# Audio_Amp.net
KiCad netlist of a schematic drawn in Altium Designer
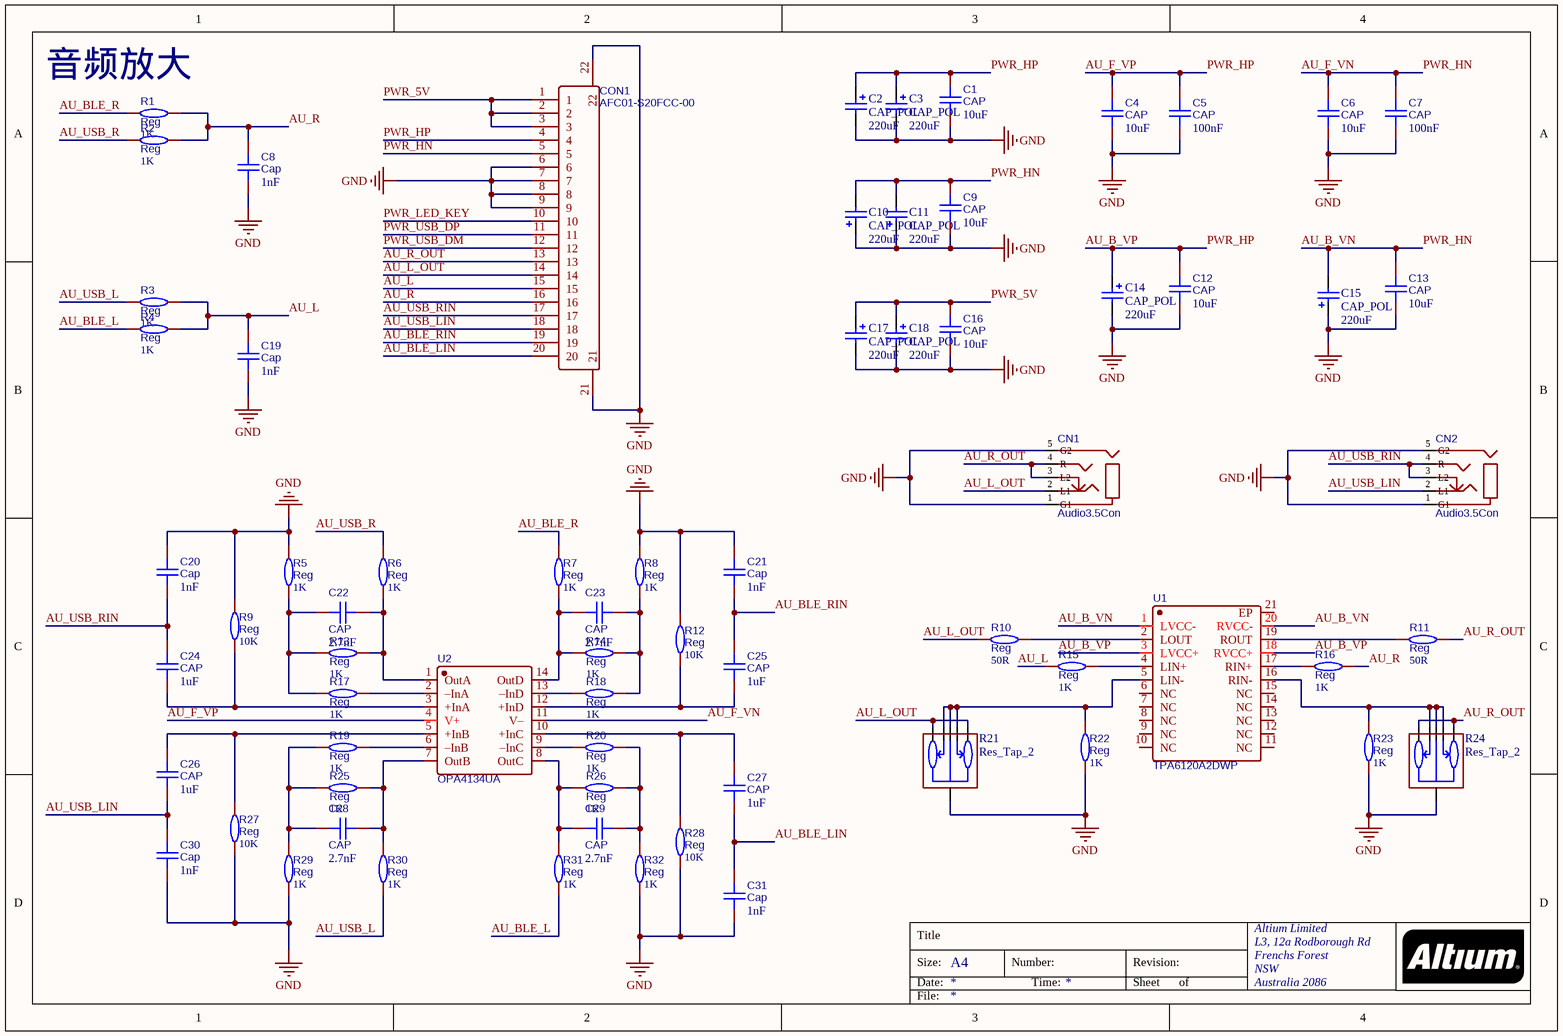
[diagram p0: Audio_Amp.SchDoc]

(export (version "E")
  (design (tool "Eeschema 10.0.6"))
  (components
    (comp (ref "C1")
      (value "CAP")
      (footprint "C0603")
      (description "Cap")
      (fields
        (field (name "BOM_SUPPLIER PART") "C302008")
        (field (name "BOM_MANUFACTURER PART") "0603B103K101CT")
        (field (name "ALTIUM_VALUE") "10uF")
        (field (name "CONTRIBUTOR") "LCSC")
      )
      (libsource (lib "Levent_lib") (part "CAP"))
    )
    (comp (ref "C2")
      (value "CAP_POL")
      (footprint "CAP_SMD_6.3mm")
      (description "极性电容")
      (fields (field (name "ALTIUM_VALUE") "220uF"))
      (libsource (lib "Levent_lib") (part "CAP_POL"))
    )
    (comp (ref "C3")
      (value "CAP_POL")
      (footprint "CAP_SMD_6.3mm")
      (description "极性电容")
      (fields (field (name "ALTIUM_VALUE") "220uF"))
      (libsource (lib "Levent_lib") (part "CAP_POL"))
    )
    (comp (ref "C4")
      (value "CAP")
      (footprint "C0603")
      (description "Cap")
      (fields
        (field (name "BOM_SUPPLIER PART") "C302008")
        (field (name "BOM_MANUFACTURER PART") "0603B103K101CT")
        (field (name "ALTIUM_VALUE") "10uF")
        (field (name "CONTRIBUTOR") "LCSC")
      )
      (libsource (lib "Levent_lib") (part "CAP"))
    )
    (comp (ref "C5")
      (value "CAP")
      (footprint "C0603")
      (description "Cap")
      (fields
        (field (name "BOM_SUPPLIER PART") "C302008")
        (field (name "BOM_MANUFACTURER PART") "0603B103K101CT")
        (field (name "ALTIUM_VALUE") "100nF")
        (field (name "CONTRIBUTOR") "LCSC")
      )
      (libsource (lib "Levent_lib") (part "CAP"))
    )
    (comp (ref "C6")
      (value "CAP")
      (footprint "C0603")
      (description "Cap")
      (fields
        (field (name "BOM_SUPPLIER PART") "C302008")
        (field (name "BOM_MANUFACTURER PART") "0603B103K101CT")
        (field (name "ALTIUM_VALUE") "10uF")
        (field (name "CONTRIBUTOR") "LCSC")
      )
      (libsource (lib "Levent_lib") (part "CAP"))
    )
    (comp (ref "C7")
      (value "CAP")
      (footprint "C0603")
      (description "Cap")
      (fields
        (field (name "BOM_SUPPLIER PART") "C302008")
        (field (name "BOM_MANUFACTURER PART") "0603B103K101CT")
        (field (name "ALTIUM_VALUE") "100nF")
        (field (name "CONTRIBUTOR") "LCSC")
      )
      (libsource (lib "Levent_lib") (part "CAP"))
    )
    (comp (ref "C8")
      (value "Cap")
      (footprint "C0603")
      (fields
        (field (name "BOM_SUPPLIER PART") "C302008")
        (field (name "BOM_MANUFACTURER PART") "0603B103K101CT")
        (field (name "ALTIUM_VALUE") "1nF")
        (field (name "CONTRIBUTOR") "LCSC")
      )
      (libsource (lib "Levent_lib") (part "CAP"))
    )
    (comp (ref "C9")
      (value "CAP")
      (footprint "C0603")
      (description "Cap")
      (fields
        (field (name "BOM_SUPPLIER PART") "C302008")
        (field (name "BOM_MANUFACTURER PART") "0603B103K101CT")
        (field (name "ALTIUM_VALUE") "10uF")
        (field (name "CONTRIBUTOR") "LCSC")
      )
      (libsource (lib "Levent_lib") (part "CAP"))
    )
    (comp (ref "C10")
      (value "CAP_POL")
      (footprint "CAP_SMD_6.3mm")
      (description "极性电容")
      (fields (field (name "ALTIUM_VALUE") "220uF"))
      (libsource (lib "Levent_lib") (part "CAP_POL"))
    )
    (comp (ref "C11")
      (value "CAP_POL")
      (footprint "CAP_SMD_6.3mm")
      (description "极性电容")
      (fields (field (name "ALTIUM_VALUE") "220uF"))
      (libsource (lib "Levent_lib") (part "CAP_POL"))
    )
    (comp (ref "C12")
      (value "CAP")
      (footprint "C0603")
      (description "Cap")
      (fields
        (field (name "BOM_SUPPLIER PART") "C302008")
        (field (name "BOM_MANUFACTURER PART") "0603B103K101CT")
        (field (name "ALTIUM_VALUE") "10uF")
        (field (name "CONTRIBUTOR") "LCSC")
      )
      (libsource (lib "Levent_lib") (part "CAP"))
    )
    (comp (ref "C13")
      (value "CAP")
      (footprint "C0603")
      (description "Cap")
      (fields
        (field (name "BOM_SUPPLIER PART") "C302008")
        (field (name "BOM_MANUFACTURER PART") "0603B103K101CT")
        (field (name "ALTIUM_VALUE") "10uF")
        (field (name "CONTRIBUTOR") "LCSC")
      )
      (libsource (lib "Levent_lib") (part "CAP"))
    )
    (comp (ref "C14")
      (value "CAP_POL")
      (footprint "CAP_SMD_6.3mm")
      (description "极性电容")
      (fields (field (name "ALTIUM_VALUE") "220uF"))
      (libsource (lib "Levent_lib") (part "CAP_POL"))
    )
    (comp (ref "C15")
      (value "CAP_POL")
      (footprint "CAP_SMD_6.3mm")
      (description "极性电容")
      (fields (field (name "ALTIUM_VALUE") "220uF"))
      (libsource (lib "Levent_lib") (part "CAP_POL"))
    )
    (comp (ref "C16")
      (value "CAP")
      (footprint "C0603")
      (description "Cap")
      (fields
        (field (name "BOM_SUPPLIER PART") "C302008")
        (field (name "BOM_MANUFACTURER PART") "0603B103K101CT")
        (field (name "ALTIUM_VALUE") "10uF")
        (field (name "CONTRIBUTOR") "LCSC")
      )
      (libsource (lib "Levent_lib") (part "CAP"))
    )
    (comp (ref "C17")
      (value "CAP_POL")
      (footprint "CAP_SMD_6.3mm")
      (description "极性电容")
      (fields (field (name "ALTIUM_VALUE") "220uF"))
      (libsource (lib "Levent_lib") (part "CAP_POL"))
    )
    (comp (ref "C18")
      (value "CAP_POL")
      (footprint "CAP_SMD_6.3mm")
      (description "极性电容")
      (fields (field (name "ALTIUM_VALUE") "220uF"))
      (libsource (lib "Levent_lib") (part "CAP_POL"))
    )
    (comp (ref "C19")
      (value "Cap")
      (footprint "C0603")
      (fields
        (field (name "BOM_SUPPLIER PART") "C302008")
        (field (name "BOM_MANUFACTURER PART") "0603B103K101CT")
        (field (name "ALTIUM_VALUE") "1nF")
        (field (name "CONTRIBUTOR") "LCSC")
      )
      (libsource (lib "Levent_lib") (part "CAP"))
    )
    (comp (ref "C20")
      (value "Cap")
      (footprint "C0603")
      (fields
        (field (name "BOM_SUPPLIER PART") "C302008")
        (field (name "BOM_MANUFACTURER PART") "0603B103K101CT")
        (field (name "ALTIUM_VALUE") "1nF")
        (field (name "CONTRIBUTOR") "LCSC")
      )
      (libsource (lib "Levent_lib") (part "CAP"))
    )
    (comp (ref "C21")
      (value "Cap")
      (footprint "C0603")
      (fields
        (field (name "BOM_SUPPLIER PART") "C302008")
        (field (name "BOM_MANUFACTURER PART") "0603B103K101CT")
        (field (name "ALTIUM_VALUE") "1nF")
        (field (name "CONTRIBUTOR") "LCSC")
      )
      (libsource (lib "Levent_lib") (part "CAP"))
    )
    (comp (ref "C22")
      (value "CAP")
      (footprint "C0603")
      (description "Cap")
      (fields
        (field (name "BOM_SUPPLIER PART") "C302008")
        (field (name "BOM_MANUFACTURER PART") "0603B103K101CT")
        (field (name "ALTIUM_VALUE") "2.7nF")
        (field (name "CONTRIBUTOR") "LCSC")
      )
      (libsource (lib "Levent_lib") (part "CAP"))
    )
    (comp (ref "C23")
      (value "CAP")
      (footprint "C0603")
      (description "Cap")
      (fields
        (field (name "BOM_SUPPLIER PART") "C302008")
        (field (name "BOM_MANUFACTURER PART") "0603B103K101CT")
        (field (name "ALTIUM_VALUE") "2.7nF")
        (field (name "CONTRIBUTOR") "LCSC")
      )
      (libsource (lib "Levent_lib") (part "CAP"))
    )
    (comp (ref "C24")
      (value "CAP")
      (footprint "C0603")
      (description "Cap")
      (fields
        (field (name "BOM_SUPPLIER PART") "C302008")
        (field (name "BOM_MANUFACTURER PART") "0603B103K101CT")
        (field (name "ALTIUM_VALUE") "1uF")
        (field (name "CONTRIBUTOR") "LCSC")
      )
      (libsource (lib "Levent_lib") (part "CAP"))
    )
    (comp (ref "C25")
      (value "CAP")
      (footprint "C0603")
      (description "Cap")
      (fields
        (field (name "BOM_SUPPLIER PART") "C302008")
        (field (name "BOM_MANUFACTURER PART") "0603B103K101CT")
        (field (name "ALTIUM_VALUE") "1uF")
        (field (name "CONTRIBUTOR") "LCSC")
      )
      (libsource (lib "Levent_lib") (part "CAP"))
    )
    (comp (ref "C26")
      (value "CAP")
      (footprint "C0603")
      (description "Cap")
      (fields
        (field (name "BOM_SUPPLIER PART") "C302008")
        (field (name "BOM_MANUFACTURER PART") "0603B103K101CT")
        (field (name "ALTIUM_VALUE") "1uF")
        (field (name "CONTRIBUTOR") "LCSC")
      )
      (libsource (lib "Levent_lib") (part "CAP"))
    )
    (comp (ref "C27")
      (value "CAP")
      (footprint "C0603")
      (description "Cap")
      (fields
        (field (name "BOM_SUPPLIER PART") "C302008")
        (field (name "BOM_MANUFACTURER PART") "0603B103K101CT")
        (field (name "ALTIUM_VALUE") "1uF")
        (field (name "CONTRIBUTOR") "LCSC")
      )
      (libsource (lib "Levent_lib") (part "CAP"))
    )
    (comp (ref "C28")
      (value "CAP")
      (footprint "C0603")
      (description "Cap")
      (fields
        (field (name "BOM_SUPPLIER PART") "C302008")
        (field (name "BOM_MANUFACTURER PART") "0603B103K101CT")
        (field (name "ALTIUM_VALUE") "2.7nF")
        (field (name "CONTRIBUTOR") "LCSC")
      )
      (libsource (lib "Levent_lib") (part "CAP"))
    )
    (comp (ref "C29")
      (value "CAP")
      (footprint "C0603")
      (description "Cap")
      (fields
        (field (name "BOM_SUPPLIER PART") "C302008")
        (field (name "BOM_MANUFACTURER PART") "0603B103K101CT")
        (field (name "ALTIUM_VALUE") "2.7nF")
        (field (name "CONTRIBUTOR") "LCSC")
      )
      (libsource (lib "Levent_lib") (part "CAP"))
    )
    (comp (ref "C30")
      (value "Cap")
      (footprint "C0603")
      (fields
        (field (name "BOM_SUPPLIER PART") "C302008")
        (field (name "BOM_MANUFACTURER PART") "0603B103K101CT")
        (field (name "ALTIUM_VALUE") "1nF")
        (field (name "CONTRIBUTOR") "LCSC")
      )
      (libsource (lib "Levent_lib") (part "CAP"))
    )
    (comp (ref "C31")
      (value "Cap")
      (footprint "C0603")
      (fields
        (field (name "BOM_SUPPLIER PART") "C302008")
        (field (name "BOM_MANUFACTURER PART") "0603B103K101CT")
        (field (name "ALTIUM_VALUE") "1nF")
        (field (name "CONTRIBUTOR") "LCSC")
      )
      (libsource (lib "Levent_lib") (part "CAP"))
    )
    (comp (ref "CN1")
      (value "Audio3.5Con")
      (footprint "Audio3.5_3Pin")
      (description "3.5mm 3Pin 音频接口")
      (fields
        (field (name "BOM_SUPPLIER PART") "C2837065")
        (field (name "BOM_MANUFACTURER PART") "PJ-393")
        (field (name "CONTRIBUTOR") "LCSC")
      )
      (libsource (lib "Levent_lib") (part "AudioCon3"))
    )
    (comp (ref "CN2")
      (value "Audio3.5Con")
      (footprint "Audio3.5_3Pin")
      (description "3.5mm 3Pin 音频接口")
      (fields
        (field (name "BOM_SUPPLIER PART") "C2837065")
        (field (name "BOM_MANUFACTURER PART") "PJ-393")
        (field (name "CONTRIBUTOR") "LCSC")
      )
      (libsource (lib "Levent_lib") (part "AudioCon3"))
    )
    (comp (ref "CON1")
      (value "AFC01-S20FCC-00")
      (footprint "FPC-SMD_20P_0.5")
      (description "FPC连接器20Pin")
      (fields (field (name "BOM_SUPPLIER PART") "C262274") (field (name "CONTRIBUTOR") "LCSC"))
      (libsource (lib "Levent_lib") (part "FPC_CONN_20"))
    )
    (comp (ref "R1")
      (value "Reg")
      (footprint "R0603")
      (description "电阻")
      (fields
        (field (name "BOM_SUPPLIER PART") "C465721")
        (field (name "BOM_MANUFACTURER PART") "AR03BTCX1002A")
        (field (name "ALTIUM_VALUE") "1K")
        (field (name "CONTRIBUTOR") "LCSC")
      )
      (libsource (lib "Levent_lib") (part "Res"))
    )
    (comp (ref "R2")
      (value "Reg")
      (footprint "R0603")
      (description "电阻")
      (fields
        (field (name "BOM_SUPPLIER PART") "C465721")
        (field (name "BOM_MANUFACTURER PART") "AR03BTCX1002A")
        (field (name "ALTIUM_VALUE") "1K")
        (field (name "CONTRIBUTOR") "LCSC")
      )
      (libsource (lib "Levent_lib") (part "Res"))
    )
    (comp (ref "R3")
      (value "Reg")
      (footprint "R0603")
      (description "电阻")
      (fields
        (field (name "BOM_SUPPLIER PART") "C465721")
        (field (name "BOM_MANUFACTURER PART") "AR03BTCX1002A")
        (field (name "ALTIUM_VALUE") "1K")
        (field (name "CONTRIBUTOR") "LCSC")
      )
      (libsource (lib "Levent_lib") (part "Res"))
    )
    (comp (ref "R4")
      (value "Reg")
      (footprint "R0603")
      (description "电阻")
      (fields
        (field (name "BOM_SUPPLIER PART") "C465721")
        (field (name "BOM_MANUFACTURER PART") "AR03BTCX1002A")
        (field (name "ALTIUM_VALUE") "1K")
        (field (name "CONTRIBUTOR") "LCSC")
      )
      (libsource (lib "Levent_lib") (part "Res"))
    )
    (comp (ref "R5")
      (value "Reg")
      (footprint "R0603")
      (description "电阻")
      (fields
        (field (name "BOM_SUPPLIER PART") "C465721")
        (field (name "BOM_MANUFACTURER PART") "AR03BTCX1002A")
        (field (name "ALTIUM_VALUE") "1K")
        (field (name "CONTRIBUTOR") "LCSC")
      )
      (libsource (lib "Levent_lib") (part "Res"))
    )
    (comp (ref "R6")
      (value "Reg")
      (footprint "R0603")
      (description "电阻")
      (fields
        (field (name "BOM_SUPPLIER PART") "C465721")
        (field (name "BOM_MANUFACTURER PART") "AR03BTCX1002A")
        (field (name "ALTIUM_VALUE") "1K")
        (field (name "CONTRIBUTOR") "LCSC")
      )
      (libsource (lib "Levent_lib") (part "Res"))
    )
    (comp (ref "R7")
      (value "Reg")
      (footprint "R0603")
      (description "电阻")
      (fields
        (field (name "BOM_SUPPLIER PART") "C465721")
        (field (name "BOM_MANUFACTURER PART") "AR03BTCX1002A")
        (field (name "ALTIUM_VALUE") "1K")
        (field (name "CONTRIBUTOR") "LCSC")
      )
      (libsource (lib "Levent_lib") (part "Res"))
    )
    (comp (ref "R8")
      (value "Reg")
      (footprint "R0603")
      (description "电阻")
      (fields
        (field (name "BOM_SUPPLIER PART") "C465721")
        (field (name "BOM_MANUFACTURER PART") "AR03BTCX1002A")
        (field (name "ALTIUM_VALUE") "1K")
        (field (name "CONTRIBUTOR") "LCSC")
      )
      (libsource (lib "Levent_lib") (part "Res"))
    )
    (comp (ref "R9")
      (value "Reg")
      (footprint "R0603")
      (description "电阻")
      (fields
        (field (name "BOM_SUPPLIER PART") "C465721")
        (field (name "BOM_MANUFACTURER PART") "AR03BTCX1002A")
        (field (name "ALTIUM_VALUE") "10K")
        (field (name "CONTRIBUTOR") "LCSC")
      )
      (libsource (lib "Levent_lib") (part "Res"))
    )
    (comp (ref "R10")
      (value "Reg")
      (footprint "R0603")
      (description "电阻")
      (fields
        (field (name "BOM_SUPPLIER PART") "C465721")
        (field (name "BOM_MANUFACTURER PART") "AR03BTCX1002A")
        (field (name "ALTIUM_VALUE") "50R")
        (field (name "CONTRIBUTOR") "LCSC")
      )
      (libsource (lib "Levent_lib") (part "Res"))
    )
    (comp (ref "R11")
      (value "Reg")
      (footprint "R0603")
      (description "电阻")
      (fields
        (field (name "BOM_SUPPLIER PART") "C465721")
        (field (name "BOM_MANUFACTURER PART") "AR03BTCX1002A")
        (field (name "ALTIUM_VALUE") "50R")
        (field (name "CONTRIBUTOR") "LCSC")
      )
      (libsource (lib "Levent_lib") (part "Res"))
    )
    (comp (ref "R12")
      (value "Reg")
      (footprint "R0603")
      (description "电阻")
      (fields
        (field (name "BOM_SUPPLIER PART") "C465721")
        (field (name "BOM_MANUFACTURER PART") "AR03BTCX1002A")
        (field (name "ALTIUM_VALUE") "10K")
        (field (name "CONTRIBUTOR") "LCSC")
      )
      (libsource (lib "Levent_lib") (part "Res"))
    )
    (comp (ref "R13")
      (value "Reg")
      (footprint "R0603")
      (description "电阻")
      (fields
        (field (name "BOM_SUPPLIER PART") "C465721")
        (field (name "BOM_MANUFACTURER PART") "AR03BTCX1002A")
        (field (name "ALTIUM_VALUE") "1K")
        (field (name "CONTRIBUTOR") "LCSC")
      )
      (libsource (lib "Levent_lib") (part "Res"))
    )
    (comp (ref "R14")
      (value "Reg")
      (footprint "R0603")
      (description "电阻")
      (fields
        (field (name "BOM_SUPPLIER PART") "C465721")
        (field (name "BOM_MANUFACTURER PART") "AR03BTCX1002A")
        (field (name "ALTIUM_VALUE") "1K")
        (field (name "CONTRIBUTOR") "LCSC")
      )
      (libsource (lib "Levent_lib") (part "Res"))
    )
    (comp (ref "R15")
      (value "Reg")
      (footprint "R0603")
      (description "电阻")
      (fields
        (field (name "BOM_SUPPLIER PART") "C465721")
        (field (name "BOM_MANUFACTURER PART") "AR03BTCX1002A")
        (field (name "ALTIUM_VALUE") "1K")
        (field (name "CONTRIBUTOR") "LCSC")
      )
      (libsource (lib "Levent_lib") (part "Res"))
    )
    (comp (ref "R16")
      (value "Reg")
      (footprint "R0603")
      (description "电阻")
      (fields
        (field (name "BOM_SUPPLIER PART") "C465721")
        (field (name "BOM_MANUFACTURER PART") "AR03BTCX1002A")
        (field (name "ALTIUM_VALUE") "1K")
        (field (name "CONTRIBUTOR") "LCSC")
      )
      (libsource (lib "Levent_lib") (part "Res"))
    )
    (comp (ref "R17")
      (value "Reg")
      (footprint "R0603")
      (description "电阻")
      (fields
        (field (name "BOM_SUPPLIER PART") "C465721")
        (field (name "BOM_MANUFACTURER PART") "AR03BTCX1002A")
        (field (name "ALTIUM_VALUE") "1K")
        (field (name "CONTRIBUTOR") "LCSC")
      )
      (libsource (lib "Levent_lib") (part "Res"))
    )
    (comp (ref "R18")
      (value "Reg")
      (footprint "R0603")
      (description "电阻")
      (fields
        (field (name "BOM_SUPPLIER PART") "C465721")
        (field (name "BOM_MANUFACTURER PART") "AR03BTCX1002A")
        (field (name "ALTIUM_VALUE") "1K")
        (field (name "CONTRIBUTOR") "LCSC")
      )
      (libsource (lib "Levent_lib") (part "Res"))
    )
    (comp (ref "R19")
      (value "Reg")
      (footprint "R0603")
      (description "电阻")
      (fields
        (field (name "BOM_SUPPLIER PART") "C465721")
        (field (name "BOM_MANUFACTURER PART") "AR03BTCX1002A")
        (field (name "ALTIUM_VALUE") "1K")
        (field (name "CONTRIBUTOR") "LCSC")
      )
      (libsource (lib "Levent_lib") (part "Res"))
    )
    (comp (ref "R20")
      (value "Reg")
      (footprint "R0603")
      (description "电阻")
      (fields
        (field (name "BOM_SUPPLIER PART") "C465721")
        (field (name "BOM_MANUFACTURER PART") "AR03BTCX1002A")
        (field (name "ALTIUM_VALUE") "1K")
        (field (name "CONTRIBUTOR") "LCSC")
      )
      (libsource (lib "Levent_lib") (part "Res"))
    )
    (comp (ref "R21")
      (value "Res_Tap_2")
      (footprint "RES_TAP_5Pin")
      (description "双联电位器")
      (libsource (lib "Levent_lib") (part "Res_Tap_2"))
    )
    (comp (ref "R22")
      (value "Reg")
      (footprint "R0603")
      (description "电阻")
      (fields
        (field (name "BOM_SUPPLIER PART") "C465721")
        (field (name "BOM_MANUFACTURER PART") "AR03BTCX1002A")
        (field (name "ALTIUM_VALUE") "1K")
        (field (name "CONTRIBUTOR") "LCSC")
      )
      (libsource (lib "Levent_lib") (part "Res"))
    )
    (comp (ref "R23")
      (value "Reg")
      (footprint "R0603")
      (description "电阻")
      (fields
        (field (name "BOM_SUPPLIER PART") "C465721")
        (field (name "BOM_MANUFACTURER PART") "AR03BTCX1002A")
        (field (name "ALTIUM_VALUE") "1K")
        (field (name "CONTRIBUTOR") "LCSC")
      )
      (libsource (lib "Levent_lib") (part "Res"))
    )
    (comp (ref "R24")
      (value "Res_Tap_2")
      (footprint "RES_TAP_5Pin")
      (description "双联电位器")
      (libsource (lib "Levent_lib") (part "Res_Tap_2"))
    )
    (comp (ref "R25")
      (value "Reg")
      (footprint "R0603")
      (description "电阻")
      (fields
        (field (name "BOM_SUPPLIER PART") "C465721")
        (field (name "BOM_MANUFACTURER PART") "AR03BTCX1002A")
        (field (name "ALTIUM_VALUE") "1K")
        (field (name "CONTRIBUTOR") "LCSC")
      )
      (libsource (lib "Levent_lib") (part "Res"))
    )
    (comp (ref "R26")
      (value "Reg")
      (footprint "R0603")
      (description "电阻")
      (fields
        (field (name "BOM_SUPPLIER PART") "C465721")
        (field (name "BOM_MANUFACTURER PART") "AR03BTCX1002A")
        (field (name "ALTIUM_VALUE") "1K")
        (field (name "CONTRIBUTOR") "LCSC")
      )
      (libsource (lib "Levent_lib") (part "Res"))
    )
    (comp (ref "R27")
      (value "Reg")
      (footprint "R0603")
      (description "电阻")
      (fields
        (field (name "BOM_SUPPLIER PART") "C465721")
        (field (name "BOM_MANUFACTURER PART") "AR03BTCX1002A")
        (field (name "ALTIUM_VALUE") "10K")
        (field (name "CONTRIBUTOR") "LCSC")
      )
      (libsource (lib "Levent_lib") (part "Res"))
    )
    (comp (ref "R28")
      (value "Reg")
      (footprint "R0603")
      (description "电阻")
      (fields
        (field (name "BOM_SUPPLIER PART") "C465721")
        (field (name "BOM_MANUFACTURER PART") "AR03BTCX1002A")
        (field (name "ALTIUM_VALUE") "10K")
        (field (name "CONTRIBUTOR") "LCSC")
      )
      (libsource (lib "Levent_lib") (part "Res"))
    )
    (comp (ref "R29")
      (value "Reg")
      (footprint "R0603")
      (description "电阻")
      (fields
        (field (name "BOM_SUPPLIER PART") "C465721")
        (field (name "BOM_MANUFACTURER PART") "AR03BTCX1002A")
        (field (name "ALTIUM_VALUE") "1K")
        (field (name "CONTRIBUTOR") "LCSC")
      )
      (libsource (lib "Levent_lib") (part "Res"))
    )
    (comp (ref "R30")
      (value "Reg")
      (footprint "R0603")
      (description "电阻")
      (fields
        (field (name "BOM_SUPPLIER PART") "C465721")
        (field (name "BOM_MANUFACTURER PART") "AR03BTCX1002A")
        (field (name "ALTIUM_VALUE") "1K")
        (field (name "CONTRIBUTOR") "LCSC")
      )
      (libsource (lib "Levent_lib") (part "Res"))
    )
    (comp (ref "R31")
      (value "Reg")
      (footprint "R0603")
      (description "电阻")
      (fields
        (field (name "BOM_SUPPLIER PART") "C465721")
        (field (name "BOM_MANUFACTURER PART") "AR03BTCX1002A")
        (field (name "ALTIUM_VALUE") "1K")
        (field (name "CONTRIBUTOR") "LCSC")
      )
      (libsource (lib "Levent_lib") (part "Res"))
    )
    (comp (ref "R32")
      (value "Reg")
      (footprint "R0603")
      (description "电阻")
      (fields
        (field (name "BOM_SUPPLIER PART") "C465721")
        (field (name "BOM_MANUFACTURER PART") "AR03BTCX1002A")
        (field (name "ALTIUM_VALUE") "1K")
        (field (name "CONTRIBUTOR") "LCSC")
      )
      (libsource (lib "Levent_lib") (part "Res"))
    )
    (comp (ref "U1")
      (value "TPA6120A2DWP")
      (footprint "HSOP-20")
      (description "耳放")
      (fields (field (name "BOM_SUPPLIER PART") "C2871054") (field (name "CONTRIBUTOR") "LCSC"))
      (libsource (lib "Levent_lib") (part "TPA6120"))
    )
    (comp (ref "U2")
      (value "OPA4134UA")
      (footprint "SOIC-14")
      (description "耳放")
      (fields (field (name "BOM_SUPPLIER PART") "C2832240") (field (name "CONTRIBUTOR") "LCSC"))
      (libsource (lib "Levent_lib") (part "OPA4134UA"))
    )
  )
  (nets
    (net (code "1") (name "/AU_BLE_L") (class "Default")
      (node (ref "R31") (pin "1") (pinfunction "1_1") (pintype "passive"))
      (node (ref "R4") (pin "2") (pinfunction "2_2") (pintype "passive"))
    )
    (net (code "2") (name "/AU_BLE_LIN") (class "Default")
      (node (ref "C27") (pin "1") (pinfunction "1_1") (pintype "passive"))
      (node (ref "C31") (pin "2") (pinfunction "2_2") (pintype "passive"))
      (node (ref "CON1") (pin "20") (pinfunction "20_20") (pintype "passive"))
    )
    (net (code "3") (name "/AU_BLE_R") (class "Default")
      (node (ref "R1") (pin "2") (pinfunction "2_2") (pintype "passive"))
      (node (ref "R7") (pin "2") (pinfunction "2_2") (pintype "passive"))
    )
    (net (code "4") (name "/AU_BLE_RIN") (class "Default")
      (node (ref "C21") (pin "1") (pinfunction "1_1") (pintype "passive"))
      (node (ref "C25") (pin "2") (pinfunction "2_2") (pintype "passive"))
      (node (ref "CON1") (pin "19") (pinfunction "19_19") (pintype "passive"))
    )
    (net (code "5") (name "/AU_B_VN") (class "Default")
      (node (ref "C10") (pin "2") (pinfunction "2_2") (pintype "passive"))
      (node (ref "C11") (pin "2") (pinfunction "2_2") (pintype "passive"))
      (node (ref "C13") (pin "2") (pinfunction "2_2") (pintype "passive"))
      (node (ref "C15") (pin "2") (pinfunction "2_2") (pintype "passive"))
      (node (ref "C6") (pin "2") (pinfunction "2_2") (pintype "passive"))
      (node (ref "C7") (pin "2") (pinfunction "2_2") (pintype "passive"))
      (node (ref "C9") (pin "2") (pinfunction "2_2") (pintype "passive"))
      (node (ref "CON1") (pin "5") (pinfunction "5_5") (pintype "passive"))
      (node (ref "U1") (pin "1") (pinfunction "LVCC-_1") (pintype "passive"))
      (node (ref "U1") (pin "20") (pinfunction "RVCC-_20") (pintype "passive"))
      (node (ref "U2") (pin "11") (pinfunction "V–_11") (pintype "passive"))
    )
    (net (code "6") (name "/AU_B_VP") (class "Default")
      (node (ref "C1") (pin "2") (pinfunction "2_2") (pintype "passive"))
      (node (ref "C12") (pin "2") (pinfunction "2_2") (pintype "passive"))
      (node (ref "C14") (pin "1") (pinfunction "1_1") (pintype "passive"))
      (node (ref "C2") (pin "1") (pinfunction "1_1") (pintype "passive"))
      (node (ref "C3") (pin "1") (pinfunction "1_1") (pintype "passive"))
      (node (ref "C4") (pin "2") (pinfunction "2_2") (pintype "passive"))
      (node (ref "C5") (pin "2") (pinfunction "2_2") (pintype "passive"))
      (node (ref "CON1") (pin "4") (pinfunction "4_4") (pintype "passive"))
      (node (ref "U1") (pin "18") (pinfunction "RVCC+_18") (pintype "passive"))
      (node (ref "U1") (pin "3") (pinfunction "LVCC+_3") (pintype "passive"))
      (node (ref "U2") (pin "4") (pinfunction "V+_4") (pintype "passive"))
    )
    (net (code "7") (name "/AU_L") (class "Default")
      (node (ref "C19") (pin "2") (pinfunction "2_2") (pintype "passive"))
      (node (ref "CON1") (pin "15") (pinfunction "15_15") (pintype "passive"))
      (node (ref "R15") (pin "1") (pinfunction "1_1") (pintype "passive"))
      (node (ref "R3") (pin "1") (pinfunction "1_1") (pintype "passive"))
      (node (ref "R4") (pin "1") (pinfunction "1_1") (pintype "passive"))
    )
    (net (code "8") (name "/AU_L_OUT") (class "Default")
      (node (ref "CN1") (pin "2") (pinfunction "L1_2") (pintype "passive"))
      (node (ref "CON1") (pin "14") (pinfunction "14_14") (pintype "passive"))
      (node (ref "R10") (pin "1") (pinfunction "1_1") (pintype "passive"))
      (node (ref "R21") (pin "4") (pinfunction "CH2B_4") (pintype "passive"))
      (node (ref "R21") (pin "5") (pinfunction "CH1B_5") (pintype "passive"))
    )
    (net (code "9") (name "/AU_R") (class "Default")
      (node (ref "C8") (pin "2") (pinfunction "2_2") (pintype "passive"))
      (node (ref "CON1") (pin "16") (pinfunction "16_16") (pintype "passive"))
      (node (ref "R1") (pin "1") (pinfunction "1_1") (pintype "passive"))
      (node (ref "R16") (pin "2") (pinfunction "2_2") (pintype "passive"))
      (node (ref "R2") (pin "1") (pinfunction "1_1") (pintype "passive"))
    )
    (net (code "10") (name "/AU_R_OUT") (class "Default")
      (node (ref "CN1") (pin "3") (pinfunction "L2_3") (pintype "passive"))
      (node (ref "CN1") (pin "4") (pinfunction "R_4") (pintype "passive"))
      (node (ref "CON1") (pin "13") (pinfunction "13_13") (pintype "passive"))
      (node (ref "R11") (pin "2") (pinfunction "2_2") (pintype "passive"))
      (node (ref "R24") (pin "4") (pinfunction "CH2B_4") (pintype "passive"))
      (node (ref "R24") (pin "5") (pinfunction "CH1B_5") (pintype "passive"))
    )
    (net (code "11") (name "/AU_USB_L") (class "Default")
      (node (ref "R3") (pin "2") (pinfunction "2_2") (pintype "passive"))
      (node (ref "R30") (pin "1") (pinfunction "1_1") (pintype "passive"))
    )
    (net (code "12") (name "/AU_USB_LIN") (class "Default")
      (node (ref "C26") (pin "2") (pinfunction "2_2") (pintype "passive"))
      (node (ref "C30") (pin "1") (pinfunction "1_1") (pintype "passive"))
      (node (ref "CN2") (pin "2") (pinfunction "L1_2") (pintype "passive"))
      (node (ref "CON1") (pin "18") (pinfunction "18_18") (pintype "passive"))
    )
    (net (code "13") (name "/AU_USB_R") (class "Default")
      (node (ref "R2") (pin "2") (pinfunction "2_2") (pintype "passive"))
      (node (ref "R6") (pin "2") (pinfunction "2_2") (pintype "passive"))
    )
    (net (code "14") (name "/AU_USB_RIN") (class "Default")
      (node (ref "C20") (pin "1") (pinfunction "1_1") (pintype "passive"))
      (node (ref "C24") (pin "1") (pinfunction "1_1") (pintype "passive"))
      (node (ref "CN2") (pin "3") (pinfunction "L2_3") (pintype "passive"))
      (node (ref "CN2") (pin "4") (pinfunction "R_4") (pintype "passive"))
      (node (ref "CON1") (pin "17") (pinfunction "17_17") (pintype "passive"))
    )
    (net (code "15") (name "/PWR_5V") (class "Default")
      (node (ref "C16") (pin "2") (pinfunction "2_2") (pintype "passive"))
      (node (ref "C17") (pin "1") (pinfunction "1_1") (pintype "passive"))
      (node (ref "C18") (pin "1") (pinfunction "1_1") (pintype "passive"))
      (node (ref "CON1") (pin "1") (pinfunction "1_1") (pintype "passive"))
      (node (ref "CON1") (pin "2") (pinfunction "2_2") (pintype "passive"))
      (node (ref "CON1") (pin "3") (pinfunction "3_3") (pintype "passive"))
    )
    (net (code "16") (name "/PWR_LED_KEY") (class "Default")
      (node (ref "CON1") (pin "10") (pinfunction "10_10") (pintype "passive"))
    )
    (net (code "17") (name "/PWR_USB_DM") (class "Default")
      (node (ref "CON1") (pin "12") (pinfunction "12_12") (pintype "passive"))
    )
    (net (code "18") (name "/PWR_USB_DP") (class "Default")
      (node (ref "CON1") (pin "11") (pinfunction "11_11") (pintype "passive"))
    )
    (net (code "19") (name "GND") (class "Default")
      (node (ref "C1") (pin "1") (pinfunction "1_1") (pintype "passive"))
      (node (ref "C10") (pin "1") (pinfunction "1_1") (pintype "passive"))
      (node (ref "C11") (pin "1") (pinfunction "1_1") (pintype "passive"))
      (node (ref "C12") (pin "1") (pinfunction "1_1") (pintype "passive"))
      (node (ref "C13") (pin "1") (pinfunction "1_1") (pintype "passive"))
      (node (ref "C14") (pin "2") (pinfunction "2_2") (pintype "passive"))
      (node (ref "C15") (pin "1") (pinfunction "1_1") (pintype "passive"))
      (node (ref "C16") (pin "1") (pinfunction "1_1") (pintype "passive"))
      (node (ref "C17") (pin "2") (pinfunction "2_2") (pintype "passive"))
      (node (ref "C18") (pin "2") (pinfunction "2_2") (pintype "passive"))
      (node (ref "C19") (pin "1") (pinfunction "1_1") (pintype "passive"))
      (node (ref "C2") (pin "2") (pinfunction "2_2") (pintype "passive"))
      (node (ref "C20") (pin "2") (pinfunction "2_2") (pintype "passive"))
      (node (ref "C21") (pin "2") (pinfunction "2_2") (pintype "passive"))
      (node (ref "C3") (pin "2") (pinfunction "2_2") (pintype "passive"))
      (node (ref "C30") (pin "2") (pinfunction "2_2") (pintype "passive"))
      (node (ref "C31") (pin "1") (pinfunction "1_1") (pintype "passive"))
      (node (ref "C4") (pin "1") (pinfunction "1_1") (pintype "passive"))
      (node (ref "C5") (pin "1") (pinfunction "1_1") (pintype "passive"))
      (node (ref "C6") (pin "1") (pinfunction "1_1") (pintype "passive"))
      (node (ref "C7") (pin "1") (pinfunction "1_1") (pintype "passive"))
      (node (ref "C8") (pin "1") (pinfunction "1_1") (pintype "passive"))
      (node (ref "C9") (pin "1") (pinfunction "1_1") (pintype "passive"))
      (node (ref "CN1") (pin "1") (pinfunction "G1_1") (pintype "passive"))
      (node (ref "CN1") (pin "5") (pinfunction "G2_5") (pintype "passive"))
      (node (ref "CN2") (pin "1") (pinfunction "G1_1") (pintype "passive"))
      (node (ref "CN2") (pin "5") (pinfunction "G2_5") (pintype "passive"))
      (node (ref "CON1") (pin "21") (pinfunction "21_21") (pintype "passive"))
      (node (ref "CON1") (pin "22") (pinfunction "22_22") (pintype "passive"))
      (node (ref "CON1") (pin "6") (pinfunction "6_6") (pintype "passive"))
      (node (ref "CON1") (pin "7") (pinfunction "7_7") (pintype "passive"))
      (node (ref "CON1") (pin "8") (pinfunction "8_8") (pintype "passive"))
      (node (ref "CON1") (pin "9") (pinfunction "9_9") (pintype "passive"))
      (node (ref "R12") (pin "1") (pinfunction "1_1") (pintype "passive"))
      (node (ref "R21") (pin "6") (pinfunction "PAD_6") (pintype "passive"))
      (node (ref "R22") (pin "1") (pinfunction "1_1") (pintype "passive"))
      (node (ref "R23") (pin "1") (pinfunction "1_1") (pintype "passive"))
      (node (ref "R24") (pin "6") (pinfunction "PAD_6") (pintype "passive"))
      (node (ref "R27") (pin "2") (pinfunction "2_2") (pintype "passive"))
      (node (ref "R28") (pin "2") (pinfunction "2_2") (pintype "passive"))
      (node (ref "R29") (pin "1") (pinfunction "1_1") (pintype "passive"))
      (node (ref "R32") (pin "1") (pinfunction "1_1") (pintype "passive"))
      (node (ref "R5") (pin "2") (pinfunction "2_2") (pintype "passive"))
      (node (ref "R8") (pin "2") (pinfunction "2_2") (pintype "passive"))
      (node (ref "R9") (pin "1") (pinfunction "1_1") (pintype "passive"))
    )
    (net (code "20") (name "Net-(C22-Pad1)") (class "Default")
      (node (ref "C22") (pin "1") (pinfunction "1_1") (pintype "passive"))
      (node (ref "R13") (pin "2") (pinfunction "2_2") (pintype "passive"))
      (node (ref "R17") (pin "2") (pinfunction "2_2") (pintype "passive"))
      (node (ref "R5") (pin "1") (pinfunction "1_1") (pintype "passive"))
    )
    (net (code "21") (name "Net-(C23-Pad2)") (class "Default")
      (node (ref "C23") (pin "2") (pinfunction "2_2") (pintype "passive"))
      (node (ref "R14") (pin "1") (pinfunction "1_1") (pintype "passive"))
      (node (ref "R18") (pin "1") (pinfunction "1_1") (pintype "passive"))
      (node (ref "R8") (pin "1") (pinfunction "1_1") (pintype "passive"))
    )
    (net (code "22") (name "Net-(C28-Pad1)") (class "Default")
      (node (ref "C28") (pin "1") (pinfunction "1_1") (pintype "passive"))
      (node (ref "R19") (pin "2") (pinfunction "2_2") (pintype "passive"))
      (node (ref "R25") (pin "2") (pinfunction "2_2") (pintype "passive"))
      (node (ref "R29") (pin "2") (pinfunction "2_2") (pintype "passive"))
    )
    (net (code "23") (name "Net-(C29-Pad2)") (class "Default")
      (node (ref "C29") (pin "2") (pinfunction "2_2") (pintype "passive"))
      (node (ref "R20") (pin "1") (pinfunction "1_1") (pintype "passive"))
      (node (ref "R26") (pin "1") (pinfunction "1_1") (pintype "passive"))
      (node (ref "R32") (pin "2") (pinfunction "2_2") (pintype "passive"))
    )
    (net (code "24") (name "Net-(R21-CH1A)") (class "Default")
      (node (ref "R21") (pin "1") (pinfunction "G_1") (pintype "passive"))
      (node (ref "R21") (pin "2") (pinfunction "CH1A_2") (pintype "passive"))
      (node (ref "R21") (pin "3") (pinfunction "CH2A_3") (pintype "passive"))
      (node (ref "R22") (pin "2") (pinfunction "2_2") (pintype "passive"))
      (node (ref "U1") (pin "5") (pinfunction "LIN-_5") (pintype "passive"))
    )
    (net (code "25") (name "Net-(R24-CH1A)") (class "Default")
      (node (ref "R23") (pin "2") (pinfunction "2_2") (pintype "passive"))
      (node (ref "R24") (pin "1") (pinfunction "G_1") (pintype "passive"))
      (node (ref "R24") (pin "2") (pinfunction "CH1A_2") (pintype "passive"))
      (node (ref "R24") (pin "3") (pinfunction "CH2A_3") (pintype "passive"))
      (node (ref "U1") (pin "16") (pinfunction "RIN-_16") (pintype "passive"))
    )
    (net (code "26") (name "Net-(U1-LIN+)") (class "Default")
      (node (ref "R15") (pin "2") (pinfunction "2_2") (pintype "passive"))
      (node (ref "U1") (pin "4") (pinfunction "LIN+_4") (pintype "passive"))
    )
    (net (code "27") (name "Net-(U1-LOUT)") (class "Default")
      (node (ref "R10") (pin "2") (pinfunction "2_2") (pintype "passive"))
      (node (ref "U1") (pin "2") (pinfunction "LOUT_2") (pintype "passive"))
    )
    (net (code "28") (name "Net-(U1-RIN+)") (class "Default")
      (node (ref "R16") (pin "1") (pinfunction "1_1") (pintype "passive"))
      (node (ref "U1") (pin "17") (pinfunction "RIN+_17") (pintype "passive"))
    )
    (net (code "29") (name "Net-(U1-ROUT)") (class "Default")
      (node (ref "R11") (pin "1") (pinfunction "1_1") (pintype "passive"))
      (node (ref "U1") (pin "19") (pinfunction "ROUT_19") (pintype "passive"))
    )
    (net (code "30") (name "Net-(U2-+InA)") (class "Default")
      (node (ref "C24") (pin "2") (pinfunction "2_2") (pintype "passive"))
      (node (ref "R9") (pin "2") (pinfunction "2_2") (pintype "passive"))
      (node (ref "U2") (pin "3") (pinfunction "+InA_3") (pintype "passive"))
    )
    (net (code "31") (name "Net-(U2-+InB)") (class "Default")
      (node (ref "C26") (pin "1") (pinfunction "1_1") (pintype "passive"))
      (node (ref "R27") (pin "1") (pinfunction "1_1") (pintype "passive"))
      (node (ref "U2") (pin "5") (pinfunction "+InB_5") (pintype "passive"))
    )
    (net (code "32") (name "Net-(U2-+InC)") (class "Default")
      (node (ref "C27") (pin "2") (pinfunction "2_2") (pintype "passive"))
      (node (ref "R28") (pin "1") (pinfunction "1_1") (pintype "passive"))
      (node (ref "U2") (pin "10") (pinfunction "+InC_10") (pintype "passive"))
    )
    (net (code "33") (name "Net-(U2-+InD)") (class "Default")
      (node (ref "C25") (pin "1") (pinfunction "1_1") (pintype "passive"))
      (node (ref "R12") (pin "2") (pinfunction "2_2") (pintype "passive"))
      (node (ref "U2") (pin "12") (pinfunction "+InD_12") (pintype "passive"))
    )
    (net (code "34") (name "Net-(U2-OutA)") (class "Default")
      (node (ref "C22") (pin "2") (pinfunction "2_2") (pintype "passive"))
      (node (ref "R13") (pin "1") (pinfunction "1_1") (pintype "passive"))
      (node (ref "R6") (pin "1") (pinfunction "1_1") (pintype "passive"))
      (node (ref "U2") (pin "1") (pinfunction "OutA_1") (pintype "passive"))
    )
    (net (code "35") (name "Net-(U2-OutB)") (class "Default")
      (node (ref "C28") (pin "2") (pinfunction "2_2") (pintype "passive"))
      (node (ref "R25") (pin "1") (pinfunction "1_1") (pintype "passive"))
      (node (ref "R30") (pin "2") (pinfunction "2_2") (pintype "passive"))
      (node (ref "U2") (pin "7") (pinfunction "OutB_7") (pintype "passive"))
    )
    (net (code "36") (name "Net-(U2-OutC)") (class "Default")
      (node (ref "C29") (pin "1") (pinfunction "1_1") (pintype "passive"))
      (node (ref "R26") (pin "2") (pinfunction "2_2") (pintype "passive"))
      (node (ref "R31") (pin "2") (pinfunction "2_2") (pintype "passive"))
      (node (ref "U2") (pin "8") (pinfunction "OutC_8") (pintype "passive"))
    )
    (net (code "37") (name "Net-(U2-OutD)") (class "Default")
      (node (ref "C23") (pin "1") (pinfunction "1_1") (pintype "passive"))
      (node (ref "R14") (pin "2") (pinfunction "2_2") (pintype "passive"))
      (node (ref "R7") (pin "1") (pinfunction "1_1") (pintype "passive"))
      (node (ref "U2") (pin "14") (pinfunction "OutD_14") (pintype "passive"))
    )
    (net (code "38") (name "Net-(U2-–InA)") (class "Default")
      (node (ref "R17") (pin "1") (pinfunction "1_1") (pintype "passive"))
      (node (ref "U2") (pin "2") (pinfunction "–InA_2") (pintype "passive"))
    )
    (net (code "39") (name "Net-(U2-–InB)") (class "Default")
      (node (ref "R19") (pin "1") (pinfunction "1_1") (pintype "passive"))
      (node (ref "U2") (pin "6") (pinfunction "–InB_6") (pintype "passive"))
    )
    (net (code "40") (name "Net-(U2-–InC)") (class "Default")
      (node (ref "R20") (pin "2") (pinfunction "2_2") (pintype "passive"))
      (node (ref "U2") (pin "9") (pinfunction "–InC_9") (pintype "passive"))
    )
    (net (code "41") (name "Net-(U2-–InD)") (class "Default")
      (node (ref "R18") (pin "2") (pinfunction "2_2") (pintype "passive"))
      (node (ref "U2") (pin "13") (pinfunction "–InD_13") (pintype "passive"))
    )
    (net (code "42") (name "unconnected-(U1-EP-Pad21)") (class "Default")
      (node (ref "U1") (pin "21") (pinfunction "EP_21") (pintype "passive"))
    )
    (net (code "43") (name "unconnected-(U1-NC-Pad6)") (class "Default")
      (node (ref "U1") (pin "6") (pinfunction "NC_6") (pintype "passive"))
    )
    (net (code "44") (name "unconnected-(U1-NC-Pad7)") (class "Default")
      (node (ref "U1") (pin "7") (pinfunction "NC_7") (pintype "passive"))
    )
    (net (code "45") (name "unconnected-(U1-NC-Pad8)") (class "Default")
      (node (ref "U1") (pin "8") (pinfunction "NC_8") (pintype "passive"))
    )
    (net (code "46") (name "unconnected-(U1-NC-Pad9)") (class "Default")
      (node (ref "U1") (pin "9") (pinfunction "NC_9") (pintype "passive"))
    )
    (net (code "47") (name "unconnected-(U1-NC-Pad10)") (class "Default")
      (node (ref "U1") (pin "10") (pinfunction "NC_10") (pintype "passive"))
    )
    (net (code "48") (name "unconnected-(U1-NC-Pad11)") (class "Default")
      (node (ref "U1") (pin "11") (pinfunction "NC_11") (pintype "passive"))
    )
    (net (code "49") (name "unconnected-(U1-NC-Pad12)") (class "Default")
      (node (ref "U1") (pin "12") (pinfunction "NC_12") (pintype "passive"))
    )
    (net (code "50") (name "unconnected-(U1-NC-Pad13)") (class "Default")
      (node (ref "U1") (pin "13") (pinfunction "NC_13") (pintype "passive"))
    )
    (net (code "51") (name "unconnected-(U1-NC-Pad14)") (class "Default")
      (node (ref "U1") (pin "14") (pinfunction "NC_14") (pintype "passive"))
    )
    (net (code "52") (name "unconnected-(U1-NC-Pad15)") (class "Default")
      (node (ref "U1") (pin "15") (pinfunction "NC_15") (pintype "passive"))
    )
  )
)
